# Connector_B.net
KiCad netlist of a schematic drawn in Altium Designer
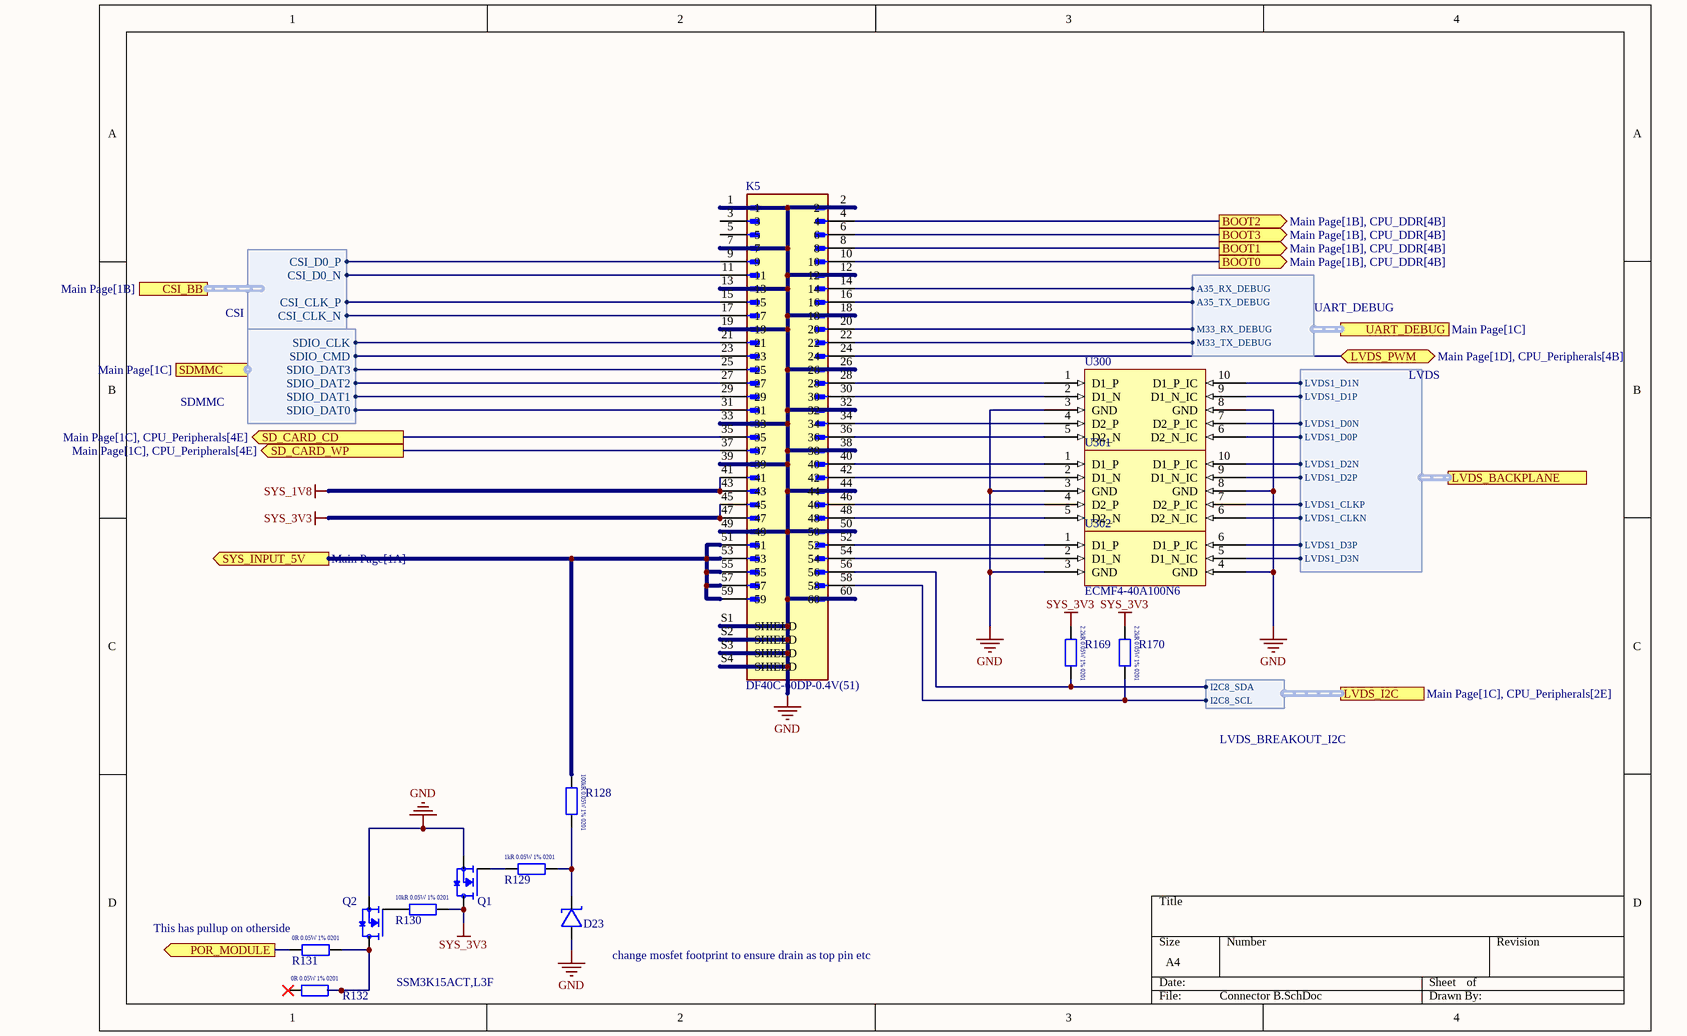
[diagram p0: Connector B.SchDoc]

(export (version "E")
  (design (tool "Eeschema 10.0.6"))
  (components
    (comp (ref "D23")
      (value "RCLAMP04041PW.C")
      (footprint "RCLAMP04041PW.C")
      (description "8V Clamp 20A (8/20µs) Ipp Tvs Diode Surface Mount 2-DFN (1x0.6)")
      (libsource (lib "Gesturelink Schematic Library") (part "RCLAMP04041PW.C"))
    )
    (comp (ref "K5")
      (value "DF40C-60DP-0.4V(51)")
      (footprint "HIROSE_DF40C-60DP-0.4V(51)")
      (description "60 Position Connector Plug, Outer Shroud Contacts Surface Mount Gold")
      (fields (field (name "MF") "Hirose Electric"))
      (libsource (lib "Gesturelink Schematic Library") (part "DF40C-60DP-0.4V(51)"))
    )
    (comp (ref "Q1")
      (value "SSM3K15ACT,L3F")
      (footprint "SSM3K15ACT")
      (description "N-Channel 30 V 100mA (Ta) 100mW (Ta) Surface Mount CST3")
      (libsource (lib "Gesturelink Schematic Library") (part "SSM3K15ACT,L3F"))
    )
    (comp (ref "Q2")
      (value "SSM3K15ACT,L3F")
      (footprint "SSM3K15ACT")
      (description "N-Channel 30 V 100mA (Ta) 100mW (Ta) Surface Mount CST3")
      (libsource (lib "Gesturelink Schematic Library") (part "SSM3K15ACT,L3F"))
    )
    (comp (ref "R128")
      (value "ERJ-1GNF1003C")
      (footprint "RESC0603X03L")
      (description "100 kOhms ±1% 0.05W, 1/20W Chip Resistor 0201 (0603 Metric) Thick Film")
      (libsource (lib "Resistors") (part "ERJ-1GNF1003C"))
    )
    (comp (ref "R129")
      (value "ERJ-1GNF1001C")
      (footprint "RESC0603X03L")
      (description "1 kOhms ±1% 0.05W, 1/20W Chip Resistor 0201 (0603 Metric) Thick Film")
      (libsource (lib "Resistors") (part "ERJ-1GNF1001C"))
    )
    (comp (ref "R130")
      (value "ERJ-1GNF1002C")
      (footprint "RESC0603X03L")
      (description "10 kOhms ±1% 0.05W, 1/20W Chip Resistor 0201 (0603 Metric) Thick Film")
      (libsource (lib "Resistors") (part "ERJ-1GNF1002C"))
    )
    (comp (ref "R131")
      (value "ERJ-1GN0R00C")
      (footprint "RESC0603X03L")
      (description "0 Ohms Jumper Chip Resistor 0201 (0603 Metric) Thick Film")
      (libsource (lib "Resistors") (part "ERJ-1GN0R00C"))
    )
    (comp (ref "R132")
      (value "ERJ-1GN0R00C")
      (footprint "RESC0603X03L")
      (description "0 Ohms Jumper Chip Resistor 0201 (0603 Metric) Thick Film")
      (libsource (lib "Resistors") (part "ERJ-1GN0R00C"))
    )
    (comp (ref "R169")
      (value "RC0201FR-072K2L")
      (footprint "RESC0603X03L")
      (description "2.2 kOhms ±1% 0.05W, 1/20W Chip Resistor 0201 (0603 Metric) Moisture Resistant Thick Film")
      (libsource (lib "Resistors") (part "RC0201FR-072K2L"))
    )
    (comp (ref "R170")
      (value "RC0201FR-072K2L")
      (footprint "RESC0603X03L")
      (description "2.2 kOhms ±1% 0.05W, 1/20W Chip Resistor 0201 (0603 Metric) Moisture Resistant Thick Film")
      (libsource (lib "Resistors") (part "RC0201FR-072K2L"))
    )
    (comp (ref "U300")
      (value "ECMF4-40A100N10")
      (footprint "ECMF4-40A100N10")
      (description "4 Line Common Mode Choke Surface Mount 100mA DCR 3Ohm (Typ)")
      (libsource (lib "Gesturelink Schematic Library") (part "ECMF4-40A100N10"))
    )
    (comp (ref "U301")
      (value "ECMF4-40A100N10")
      (footprint "ECMF4-40A100N10")
      (description "4 Line Common Mode Choke Surface Mount 100mA DCR 3Ohm (Typ)")
      (libsource (lib "Gesturelink Schematic Library") (part "ECMF4-40A100N10"))
    )
    (comp (ref "U302")
      (value "ECMF4-40A100N6")
      (footprint "ECMF2-40A100N6")
      (description "2 Line Common Mode Choke Surface Mount 100mA DCR 3Ohm (Typ)")
      (libsource (lib "Gesturelink Schematic Library") (part "ECMF4-40A100N6"))
    )
  )
  (nets
    (net (code "6") (name "/A35_RX_DEBUG") (class "Default")
      (node (ref "K5") (pin "14") (pinfunction "14_14") (pintype "passive"))
    )
    (net (code "7") (name "/A35_TX_DEBUG") (class "Default")
      (node (ref "K5") (pin "16") (pinfunction "16_16") (pintype "passive"))
    )
    (net (code "8") (name "/BOOT0") (class "Default")
      (node (ref "K5") (pin "10") (pinfunction "10_10") (pintype "passive"))
    )
    (net (code "9") (name "/BOOT1") (class "Default")
      (node (ref "K5") (pin "8") (pinfunction "8_8") (pintype "passive"))
    )
    (net (code "10") (name "/BOOT2") (class "Default")
      (node (ref "K5") (pin "4") (pinfunction "4_4") (pintype "passive"))
    )
    (net (code "11") (name "/BOOT3") (class "Default")
      (node (ref "K5") (pin "6") (pinfunction "6_6") (pintype "passive"))
    )
    (net (code "12") (name "/CSI_CLK_N") (class "Default")
      (node (ref "K5") (pin "17") (pinfunction "17_17") (pintype "passive"))
    )
    (net (code "13") (name "/CSI_CLK_P") (class "Default")
      (node (ref "K5") (pin "15") (pinfunction "15_15") (pintype "passive"))
    )
    (net (code "14") (name "/CSI_D0_N") (class "Default")
      (node (ref "K5") (pin "11") (pinfunction "11_11") (pintype "passive"))
    )
    (net (code "15") (name "/CSI_D0_P") (class "Default")
      (node (ref "K5") (pin "9") (pinfunction "9_9") (pintype "passive"))
    )
    (net (code "16") (name "/I2C8_SCL") (class "Default")
      (node (ref "K5") (pin "58") (pinfunction "58_58") (pintype "passive"))
      (node (ref "R170") (pin "2") (pinfunction "2_2") (pintype "passive"))
    )
    (net (code "17") (name "/I2C8_SDA") (class "Default")
      (node (ref "K5") (pin "56") (pinfunction "56_56") (pintype "passive"))
      (node (ref "R169") (pin "2") (pinfunction "2_2") (pintype "passive"))
    )
    (net (code "18") (name "/LVDS1_CLKN") (class "Default")
      (node (ref "U301") (pin "6") (pinfunction "D2_N_IC_6") (pintype "input"))
    )
    (net (code "19") (name "/LVDS1_CLKP") (class "Default")
      (node (ref "U301") (pin "7") (pinfunction "D2_P_IC_7") (pintype "input"))
    )
    (net (code "20") (name "/LVDS1_D0N") (class "Default")
      (node (ref "U300") (pin "7") (pinfunction "D2_P_IC_7") (pintype "input"))
    )
    (net (code "21") (name "/LVDS1_D0P") (class "Default")
      (node (ref "U300") (pin "6") (pinfunction "D2_N_IC_6") (pintype "input"))
    )
    (net (code "22") (name "/LVDS1_D1N") (class "Default")
      (node (ref "U300") (pin "10") (pinfunction "D1_P_IC_10") (pintype "input"))
    )
    (net (code "23") (name "/LVDS1_D1P") (class "Default")
      (node (ref "U300") (pin "9") (pinfunction "D1_N_IC_9") (pintype "input"))
    )
    (net (code "24") (name "/LVDS1_D2N") (class "Default")
      (node (ref "U301") (pin "10") (pinfunction "D1_P_IC_10") (pintype "input"))
    )
    (net (code "25") (name "/LVDS1_D2P") (class "Default")
      (node (ref "U301") (pin "9") (pinfunction "D1_N_IC_9") (pintype "input"))
    )
    (net (code "26") (name "/LVDS1_D3N") (class "Default")
      (node (ref "U302") (pin "5") (pinfunction "D1_N_IC_5") (pintype "input"))
    )
    (net (code "27") (name "/LVDS1_D3P") (class "Default")
      (node (ref "U302") (pin "6") (pinfunction "D1_P_IC_6") (pintype "input"))
    )
    (net (code "28") (name "/LVDS_PWM") (class "Default")
      (node (ref "K5") (pin "24") (pinfunction "24_24") (pintype "passive"))
    )
    (net (code "29") (name "/M33_RX_DEBUG") (class "Default")
      (node (ref "K5") (pin "20") (pinfunction "20_20") (pintype "passive"))
    )
    (net (code "30") (name "/M33_TX_DEBUG") (class "Default")
      (node (ref "K5") (pin "22") (pinfunction "22_22") (pintype "passive"))
    )
    (net (code "31") (name "/POR_MODULE") (class "Default")
      (node (ref "R131") (pin "1") (pinfunction "1_1") (pintype "passive"))
    )
    (net (code "32") (name "/SDIO_CLK") (class "Default")
      (node (ref "K5") (pin "21") (pinfunction "21_21") (pintype "passive"))
    )
    (net (code "33") (name "/SDIO_CMD") (class "Default")
      (node (ref "K5") (pin "23") (pinfunction "23_23") (pintype "passive"))
    )
    (net (code "34") (name "/SDIO_DAT0") (class "Default")
      (node (ref "K5") (pin "31") (pinfunction "31_31") (pintype "passive"))
    )
    (net (code "35") (name "/SDIO_DAT1") (class "Default")
      (node (ref "K5") (pin "29") (pinfunction "29_29") (pintype "passive"))
    )
    (net (code "36") (name "/SDIO_DAT2") (class "Default")
      (node (ref "K5") (pin "27") (pinfunction "27_27") (pintype "passive"))
    )
    (net (code "37") (name "/SDIO_DAT3") (class "Default")
      (node (ref "K5") (pin "25") (pinfunction "25_25") (pintype "passive"))
    )
    (net (code "38") (name "/SD_CARD_CD") (class "Default")
      (node (ref "K5") (pin "35") (pinfunction "35_35") (pintype "passive"))
    )
    (net (code "39") (name "/SD_CARD_WP") (class "Default")
      (node (ref "K5") (pin "37") (pinfunction "37_37") (pintype "passive"))
    )
    (net (code "40") (name "/SYS_INPUT_5V") (class "Default")
      (node (ref "K5") (pin "51") (pinfunction "51_51") (pintype "passive"))
      (node (ref "K5") (pin "53") (pinfunction "53_53") (pintype "passive"))
      (node (ref "K5") (pin "55") (pinfunction "55_55") (pintype "passive"))
      (node (ref "K5") (pin "57") (pinfunction "57_57") (pintype "passive"))
      (node (ref "K5") (pin "59") (pinfunction "59_59") (pintype "passive"))
      (node (ref "R128") (pin "1") (pinfunction "1_1") (pintype "passive"))
    )
    (net (code "46") (name "GND") (class "Default")
      (node (ref "D23") (pin "1") (pinfunction "16_1") (pintype "passive"))
      (node (ref "K5") (pin "1") (pinfunction "1_1") (pintype "passive"))
      (node (ref "K5") (pin "12") (pinfunction "12_12") (pintype "passive"))
      (node (ref "K5") (pin "13") (pinfunction "13_13") (pintype "passive"))
      (node (ref "K5") (pin "18") (pinfunction "18_18") (pintype "passive"))
      (node (ref "K5") (pin "19") (pinfunction "19_19") (pintype "passive"))
      (node (ref "K5") (pin "2") (pinfunction "2_2") (pintype "passive"))
      (node (ref "K5") (pin "26") (pinfunction "26_26") (pintype "passive"))
      (node (ref "K5") (pin "32") (pinfunction "32_32") (pintype "passive"))
      (node (ref "K5") (pin "33") (pinfunction "33_33") (pintype "passive"))
      (node (ref "K5") (pin "38") (pinfunction "38_38") (pintype "passive"))
      (node (ref "K5") (pin "39") (pinfunction "39_39") (pintype "passive"))
      (node (ref "K5") (pin "44") (pinfunction "44_44") (pintype "passive"))
      (node (ref "K5") (pin "49") (pinfunction "49_49") (pintype "passive"))
      (node (ref "K5") (pin "50") (pinfunction "50_50") (pintype "passive"))
      (node (ref "K5") (pin "60") (pinfunction "60_60") (pintype "passive"))
      (node (ref "K5") (pin "7") (pinfunction "7_7") (pintype "passive"))
      (node (ref "K5") (pin "S1") (pinfunction "SHIELD_S1") (pintype "passive"))
      (node (ref "K5") (pin "S2") (pinfunction "SHIELD_S2") (pintype "passive"))
      (node (ref "K5") (pin "S3") (pinfunction "SHIELD_S3") (pintype "passive"))
      (node (ref "K5") (pin "S4") (pinfunction "SHIELD_S4") (pintype "passive"))
      (node (ref "Q1") (pin "3") (pinfunction "S_3") (pintype "passive"))
      (node (ref "Q2") (pin "3") (pinfunction "S_3") (pintype "passive"))
      (node (ref "U300") (pin "3") (pinfunction "GND_3") (pintype "input"))
      (node (ref "U300") (pin "8") (pinfunction "GND_8") (pintype "input"))
      (node (ref "U301") (pin "3") (pinfunction "GND_3") (pintype "input"))
      (node (ref "U301") (pin "8") (pinfunction "GND_8") (pintype "input"))
      (node (ref "U302") (pin "3") (pinfunction "GND_3") (pintype "input"))
      (node (ref "U302") (pin "4") (pinfunction "GND_4") (pintype "input"))
    )
    (net (code "47") (name "Net-(D23-16-Pad2)") (class "Default")
      (node (ref "D23") (pin "2") (pinfunction "16_2") (pintype "passive"))
      (node (ref "R128") (pin "2") (pinfunction "2_2") (pintype "passive"))
      (node (ref "R129") (pin "2") (pinfunction "2_2") (pintype "passive"))
    )
    (net (code "48") (name "Net-(Q1-G)") (class "Default")
      (node (ref "Q1") (pin "1") (pinfunction "G_1") (pintype "passive"))
      (node (ref "R129") (pin "1") (pinfunction "1_1") (pintype "passive"))
    )
    (net (code "49") (name "Net-(Q2-D)") (class "Default")
      (node (ref "Q2") (pin "2") (pinfunction "D_2") (pintype "passive"))
      (node (ref "R131") (pin "2") (pinfunction "2_2") (pintype "passive"))
      (node (ref "R132") (pin "2") (pinfunction "2_2") (pintype "passive"))
    )
    (net (code "50") (name "Net-(Q2-G)") (class "Default")
      (node (ref "Q2") (pin "1") (pinfunction "G_1") (pintype "passive"))
      (node (ref "R130") (pin "1") (pinfunction "1_1") (pintype "passive"))
    )
    (net (code "51") (name "Net-(U300-D1_N)") (class "Default")
      (node (ref "K5") (pin "30") (pinfunction "30_30") (pintype "passive"))
      (node (ref "U300") (pin "2") (pinfunction "D1_N_2") (pintype "input"))
    )
    (net (code "52") (name "Net-(U300-D1_P)") (class "Default")
      (node (ref "K5") (pin "28") (pinfunction "28_28") (pintype "passive"))
      (node (ref "U300") (pin "1") (pinfunction "D1_P_1") (pintype "input"))
    )
    (net (code "53") (name "Net-(U300-D2_N)") (class "Default")
      (node (ref "K5") (pin "36") (pinfunction "36_36") (pintype "passive"))
      (node (ref "U300") (pin "5") (pinfunction "D2_N_5") (pintype "input"))
    )
    (net (code "54") (name "Net-(U300-D2_P)") (class "Default")
      (node (ref "K5") (pin "34") (pinfunction "34_34") (pintype "passive"))
      (node (ref "U300") (pin "4") (pinfunction "D2_P_4") (pintype "input"))
    )
    (net (code "55") (name "Net-(U301-D1_N)") (class "Default")
      (node (ref "K5") (pin "42") (pinfunction "42_42") (pintype "passive"))
      (node (ref "U301") (pin "2") (pinfunction "D1_N_2") (pintype "input"))
    )
    (net (code "56") (name "Net-(U301-D1_P)") (class "Default")
      (node (ref "K5") (pin "40") (pinfunction "40_40") (pintype "passive"))
      (node (ref "U301") (pin "1") (pinfunction "D1_P_1") (pintype "input"))
    )
    (net (code "57") (name "Net-(U301-D2_N)") (class "Default")
      (node (ref "K5") (pin "48") (pinfunction "48_48") (pintype "passive"))
      (node (ref "U301") (pin "5") (pinfunction "D2_N_5") (pintype "input"))
    )
    (net (code "58") (name "Net-(U301-D2_P)") (class "Default")
      (node (ref "K5") (pin "46") (pinfunction "46_46") (pintype "passive"))
      (node (ref "U301") (pin "4") (pinfunction "D2_P_4") (pintype "input"))
    )
    (net (code "59") (name "Net-(U302-D1_N)") (class "Default")
      (node (ref "K5") (pin "54") (pinfunction "54_54") (pintype "passive"))
      (node (ref "U302") (pin "2") (pinfunction "D1_N_2") (pintype "input"))
    )
    (net (code "60") (name "Net-(U302-D1_P)") (class "Default")
      (node (ref "K5") (pin "52") (pinfunction "52_52") (pintype "passive"))
      (node (ref "U302") (pin "1") (pinfunction "D1_P_1") (pintype "input"))
    )
    (net (code "61") (name "SYS_1V8") (class "Default")
      (node (ref "K5") (pin "41") (pinfunction "41_41") (pintype "passive"))
      (node (ref "K5") (pin "43") (pinfunction "43_43") (pintype "passive"))
    )
    (net (code "62") (name "SYS_3V3") (class "Default")
      (node (ref "K5") (pin "45") (pinfunction "45_45") (pintype "passive"))
      (node (ref "K5") (pin "47") (pinfunction "47_47") (pintype "passive"))
      (node (ref "Q1") (pin "2") (pinfunction "D_2") (pintype "passive"))
      (node (ref "R130") (pin "2") (pinfunction "2_2") (pintype "passive"))
      (node (ref "R169") (pin "1") (pinfunction "1_1") (pintype "passive"))
      (node (ref "R170") (pin "1") (pinfunction "1_1") (pintype "passive"))
    )
    (net (code "63") (name "unconnected-(K5-Pad3)") (class "Default")
      (node (ref "K5") (pin "3") (pinfunction "3_3") (pintype "passive"))
    )
    (net (code "64") (name "unconnected-(K5-Pad5)") (class "Default")
      (node (ref "K5") (pin "5") (pinfunction "5_5") (pintype "passive"))
    )
    (net (code "65") (name "unconnected-(R132-Pad1)") (class "Default")
      (node (ref "R132") (pin "1") (pinfunction "1_1") (pintype "passive+no_connect"))
    )
  )
)
